# POWER_SUPPLY.net
KiCad netlist of a schematic drawn in Altium Designer
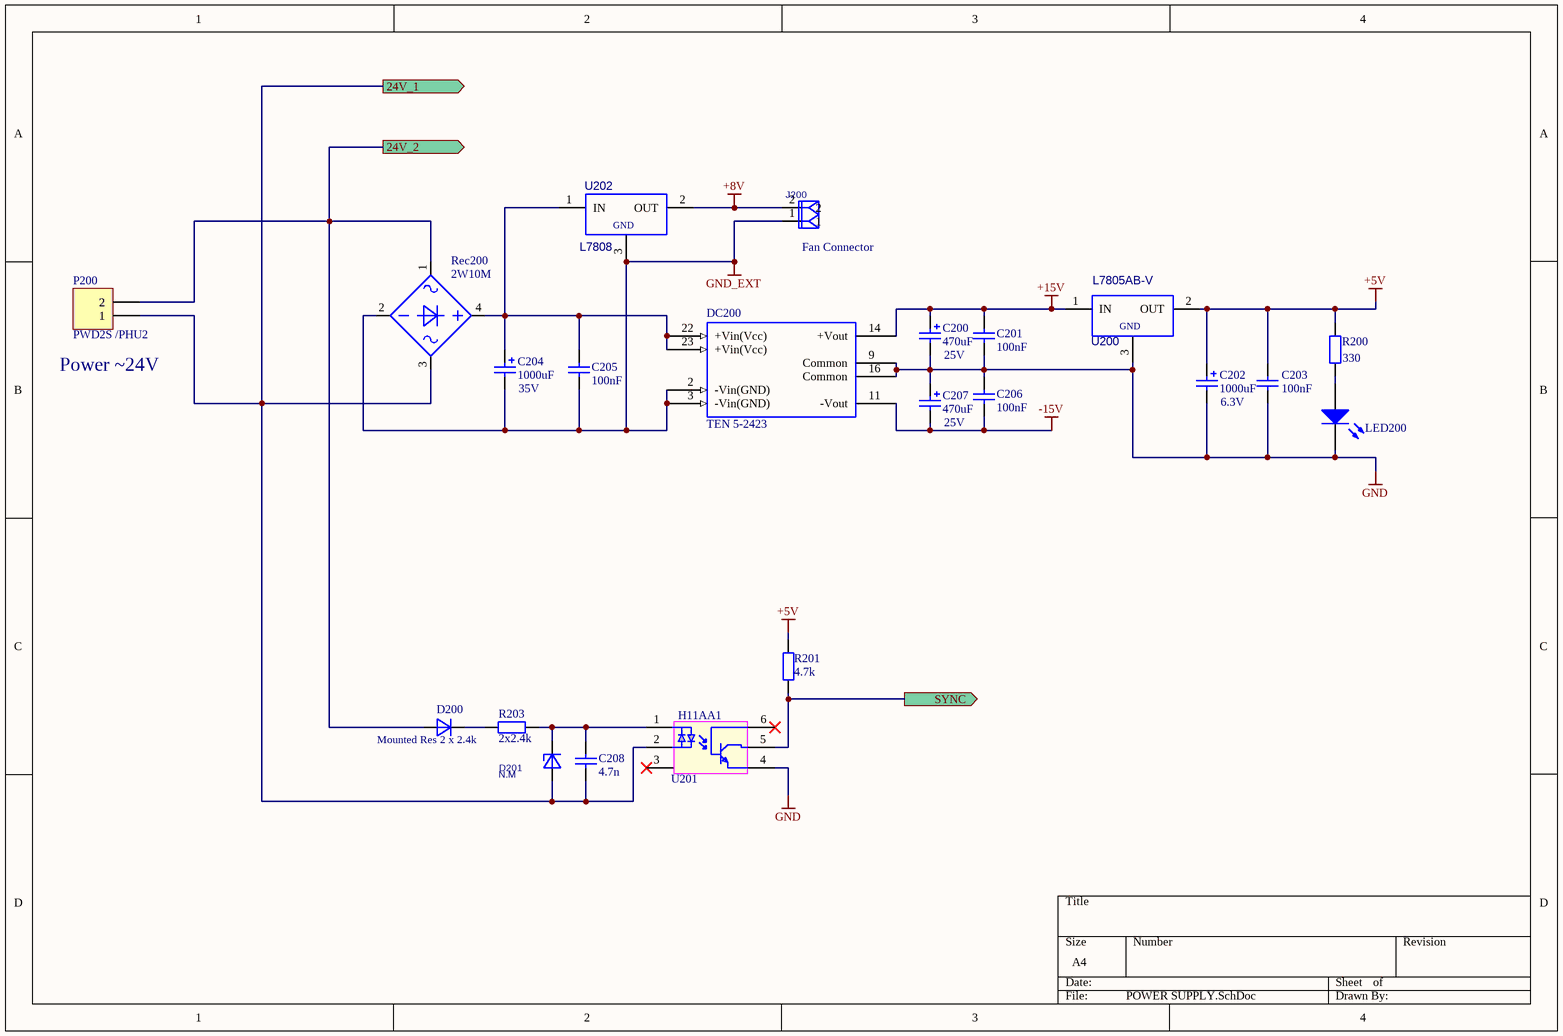
[diagram p0: POWER SUPPLY.SchDoc]

(export (version "E")
  (design (tool "Eeschema 10.0.6"))
  (components
    (comp (ref "C200")
      (value "470uF")
      (footprint "Cap Electrolyt 7")
      (fields (field (name "VOLTAGE") "25V") (field (name "Comment") "Cap"))
      (libsource (lib "Capacitors") (part "Cap pol"))
    )
    (comp (ref "C201")
      (value "100nF")
      (footprint "3216[1206]")
      (fields (field (name "Comment") "Cap 1206"))
      (libsource (lib "Capacitors") (part "Cap 1206"))
    )
    (comp (ref "C202")
      (value "1000uF")
      (footprint "Cap Electrolyt 7")
      (fields (field (name "VOLTAGE") "6.3V") (field (name "Comment") "Cap"))
      (libsource (lib "Capacitors") (part "Cap pol"))
    )
    (comp (ref "C203")
      (value "100nF")
      (footprint "3216[1206]")
      (fields (field (name "Comment") "Cap 1206"))
      (libsource (lib "Capacitors") (part "Cap 1206"))
    )
    (comp (ref "C204")
      (value "1000uF")
      (footprint "Cap Electrolyt 7")
      (fields (field (name "VOLTAGE") "35V") (field (name "Comment") "Cap"))
      (libsource (lib "Capacitors") (part "Cap pol"))
    )
    (comp (ref "C205")
      (value "100nF")
      (footprint "3216[1206]")
      (fields (field (name "Comment") "Cap 1206"))
      (libsource (lib "Capacitors") (part "Cap 1206"))
    )
    (comp (ref "C206")
      (value "100nF")
      (footprint "3216[1206]")
      (fields (field (name "Comment") "Cap 1206"))
      (libsource (lib "Capacitors") (part "Cap 1206"))
    )
    (comp (ref "C207")
      (value "470uF")
      (footprint "Cap Electrolyt 7")
      (fields (field (name "VOLTAGE") "25V") (field (name "Comment") "Cap"))
      (libsource (lib "Capacitors") (part "Cap pol"))
    )
    (comp (ref "C208")
      (value "4.7n")
      (footprint "3216[1206]")
      (fields (field (name "Comment") "Cap 1206"))
      (libsource (lib "Capacitors") (part "Cap 1206"))
    )
    (comp (ref "D200")
      (value "Mounted Res 2 x 2.4k")
      (footprint "D_MINIMELF_LL4148")
      (fields (field (name "Comment") "LL4148"))
      (libsource (lib "Diode") (part "LL4148"))
    )
    (comp (ref "D201")
      (value "N.M")
      (footprint "D_MINIMELF_BZV55C5V1(Primary)")
      (description "Voltage regulator diode")
      (fields (field (name "MANUFACTURER") "Any") (field (name "Comment") "BZV55C5V1"))
      (libsource (lib "Zener") (part "BZV55C5V1"))
    )
    (comp (ref "DC200")
      (value "TEN 5-2423")
      (footprint "DIP24_TRACO")
      (libsource (lib "DC-DC") (part "TEN 5-2423"))
    )
    (comp (ref "J200") (value "SIP2") (footprint "SIP2") (libsource (lib "DMB20") (part "SIP2")))
    (comp (ref "LED200") (value "LED") (footprint "LED_1206") (libsource (lib "LED") (part "LED")))
    (comp (ref "P200")
      (value "PWD2S /PHU2")
      (footprint "PWD2S /PHU2")
      (libsource (lib "Connector") (part "PWD2S /PHU2"))
    )
    (comp (ref "R200")
      (value "330")
      (footprint "3216[1206]")
      (fields (field (name "Comment") "RES"))
      (libsource (lib "Resistor") (part "RES 1"))
    )
    (comp (ref "R201")
      (value "4.7k")
      (footprint "3216[1206]")
      (fields (field (name "Comment") "RES"))
      (libsource (lib "Resistor") (part "RES 1"))
    )
    (comp (ref "R203")
      (value "2x2.4k")
      (footprint "3216[1206]")
      (fields (field (name "Comment") "RES"))
      (libsource (lib "") (part "RES 1_1"))
    )
    (comp (ref "Rec200")
      (value "2W10M")
      (footprint "WOB_2WXX[X]M")
      (description "Rectifier")
      (libsource (lib "Diode") (part "2W10M"))
    )
    (comp (ref "U200")
      (value "L7805AB-V")
      (footprint "SFM-T3/E10.4V_L7805AC-V(Primary)")
      (description "Precision 1A Regulator")
      (fields (field (name "Comment") "L7805AC-V"))
      (libsource (lib "Voltage_Regulator") (part "L7805AC-V"))
    )
    (comp (ref "U201") (value "H11AA1") (footprint "DIP6") (libsource (lib "Optocoupler") (part "H11AA1")))
    (comp (ref "U202")
      (value "L7808")
      (footprint "SFM-T3/E10.4V_L7805AC-V(Primary)")
      (description "Precision 1A Regulator")
      (fields (field (name "Comment") "L7805AC-V"))
      (libsource (lib "Voltage_Regulator") (part "L7805AC-V"))
    )
  )
  (nets
    (net (code "1") (name "+5V") (class "Default")
      (node (ref "C202") (pin "1") (pinfunction "1_1") (pintype "passive"))
      (node (ref "C203") (pin "2") (pinfunction "2_2") (pintype "passive"))
      (node (ref "R200") (pin "1") (pinfunction "1_1") (pintype "passive"))
      (node (ref "R201") (pin "1") (pinfunction "1_1") (pintype "passive"))
      (node (ref "U200") (pin "2") (pinfunction "OUT_2") (pintype "power_in"))
    )
    (net (code "2") (name "+8V") (class "Default")
      (node (ref "J200") (pin "2") (pinfunction "2_2") (pintype "passive"))
      (node (ref "U202") (pin "2") (pinfunction "OUT_2") (pintype "power_in"))
    )
    (net (code "3") (name "+15V") (class "Default")
      (node (ref "C200") (pin "1") (pinfunction "1_1") (pintype "passive"))
      (node (ref "C201") (pin "2") (pinfunction "2_2") (pintype "passive"))
      (node (ref "DC200") (pin "14") (pinfunction "+Vout_14") (pintype "power_in"))
      (node (ref "U200") (pin "1") (pinfunction "IN_1") (pintype "power_in"))
    )
    (net (code "4") (name "-15V") (class "Default")
      (node (ref "C206") (pin "1") (pinfunction "1_1") (pintype "passive"))
      (node (ref "C207") (pin "2") (pinfunction "2_2") (pintype "passive"))
      (node (ref "DC200") (pin "11") (pinfunction "-Vout_11") (pintype "power_in"))
    )
    (net (code "5") (name "/24V_1") (class "Default")
      (node (ref "C208") (pin "1") (pinfunction "1_1") (pintype "passive"))
      (node (ref "D201") (pin "A") (pintype "passive"))
      (node (ref "P200") (pin "1") (pinfunction "1_1") (pintype "passive"))
      (node (ref "Rec200") (pin "3") (pinfunction "AC2_3") (pintype "passive"))
      (node (ref "U201") (pin "2") (pinfunction "2_2") (pintype "passive"))
    )
    (net (code "6") (name "/24V_2") (class "Default")
      (node (ref "D200") (pin "A") (pintype "passive"))
      (node (ref "P200") (pin "2") (pinfunction "2_2") (pintype "passive"))
      (node (ref "Rec200") (pin "1") (pinfunction "AC1_1") (pintype "passive"))
    )
    (net (code "7") (name "/SYNC") (class "Default")
      (node (ref "R201") (pin "2") (pinfunction "2_2") (pintype "passive"))
      (node (ref "U201") (pin "5") (pinfunction "5_5") (pintype "passive"))
    )
    (net (code "8") (name "GND") (class "Default")
      (node (ref "C200") (pin "2") (pinfunction "2_2") (pintype "passive"))
      (node (ref "C201") (pin "1") (pinfunction "1_1") (pintype "passive"))
      (node (ref "C202") (pin "2") (pinfunction "2_2") (pintype "passive"))
      (node (ref "C203") (pin "1") (pinfunction "1_1") (pintype "passive"))
      (node (ref "C206") (pin "2") (pinfunction "2_2") (pintype "passive"))
      (node (ref "C207") (pin "1") (pinfunction "1_1") (pintype "passive"))
      (node (ref "DC200") (pin "16") (pinfunction "Common_16") (pintype "power_in"))
      (node (ref "DC200") (pin "9") (pinfunction "Common_9") (pintype "passive"))
      (node (ref "LED200") (pin "K") (pinfunction "K_K") (pintype "passive"))
      (node (ref "U200") (pin "3") (pinfunction "GND_3") (pintype "power_in"))
      (node (ref "U201") (pin "4") (pinfunction "4_4") (pintype "passive"))
    )
    (net (code "9") (name "GND_EXT") (class "Default")
      (node (ref "C204") (pin "2") (pinfunction "2_2") (pintype "passive"))
      (node (ref "C205") (pin "1") (pinfunction "1_1") (pintype "passive"))
      (node (ref "DC200") (pin "2") (pinfunction "-Vin(GND)_2") (pintype "input"))
      (node (ref "DC200") (pin "3") (pinfunction "-Vin(GND)_3") (pintype "input"))
      (node (ref "J200") (pin "1") (pinfunction "1_1") (pintype "passive"))
      (node (ref "Rec200") (pin "2") (pinfunction "-_2") (pintype "passive"))
      (node (ref "U202") (pin "3") (pinfunction "GND_3") (pintype "power_in"))
    )
    (net (code "10") (name "Net-(C208-Pad2)") (class "Default")
      (node (ref "C208") (pin "2") (pinfunction "2_2") (pintype "passive"))
      (node (ref "D201") (pin "K") (pintype "passive"))
      (node (ref "R203") (pin "2") (pinfunction "2_2") (pintype "passive"))
      (node (ref "U201") (pin "1") (pinfunction "1_1") (pintype "passive"))
    )
    (net (code "11") (name "Net-(D200-PadK)") (class "Default")
      (node (ref "D200") (pin "K") (pintype "passive"))
      (node (ref "R203") (pin "1") (pinfunction "1_1") (pintype "passive"))
    )
    (net (code "12") (name "Net-(LED200-PadA)") (class "Default")
      (node (ref "LED200") (pin "A") (pinfunction "A_A") (pintype "passive"))
      (node (ref "R200") (pin "2") (pinfunction "2_2") (pintype "passive"))
    )
    (net (code "13") (name "Net-(Rec200-+)") (class "Default")
      (node (ref "C204") (pin "1") (pinfunction "1_1") (pintype "passive"))
      (node (ref "C205") (pin "2") (pinfunction "2_2") (pintype "passive"))
      (node (ref "DC200") (pin "22") (pinfunction "+Vin(Vcc)_22") (pintype "input"))
      (node (ref "DC200") (pin "23") (pinfunction "+Vin(Vcc)_23") (pintype "input"))
      (node (ref "Rec200") (pin "4") (pinfunction "+_4") (pintype "passive"))
      (node (ref "U202") (pin "1") (pinfunction "IN_1") (pintype "power_in"))
    )
    (net (code "14") (name "unconnected-(U201-Pad3)") (class "Default")
      (node (ref "U201") (pin "3") (pinfunction "3_3") (pintype "passive+no_connect"))
    )
    (net (code "15") (name "unconnected-(U201-Pad6)") (class "Default")
      (node (ref "U201") (pin "6") (pinfunction "6_6") (pintype "passive+no_connect"))
    )
  )
)
